# AmazonDash.net
KiCad netlist of a schematic drawn in EAGLE
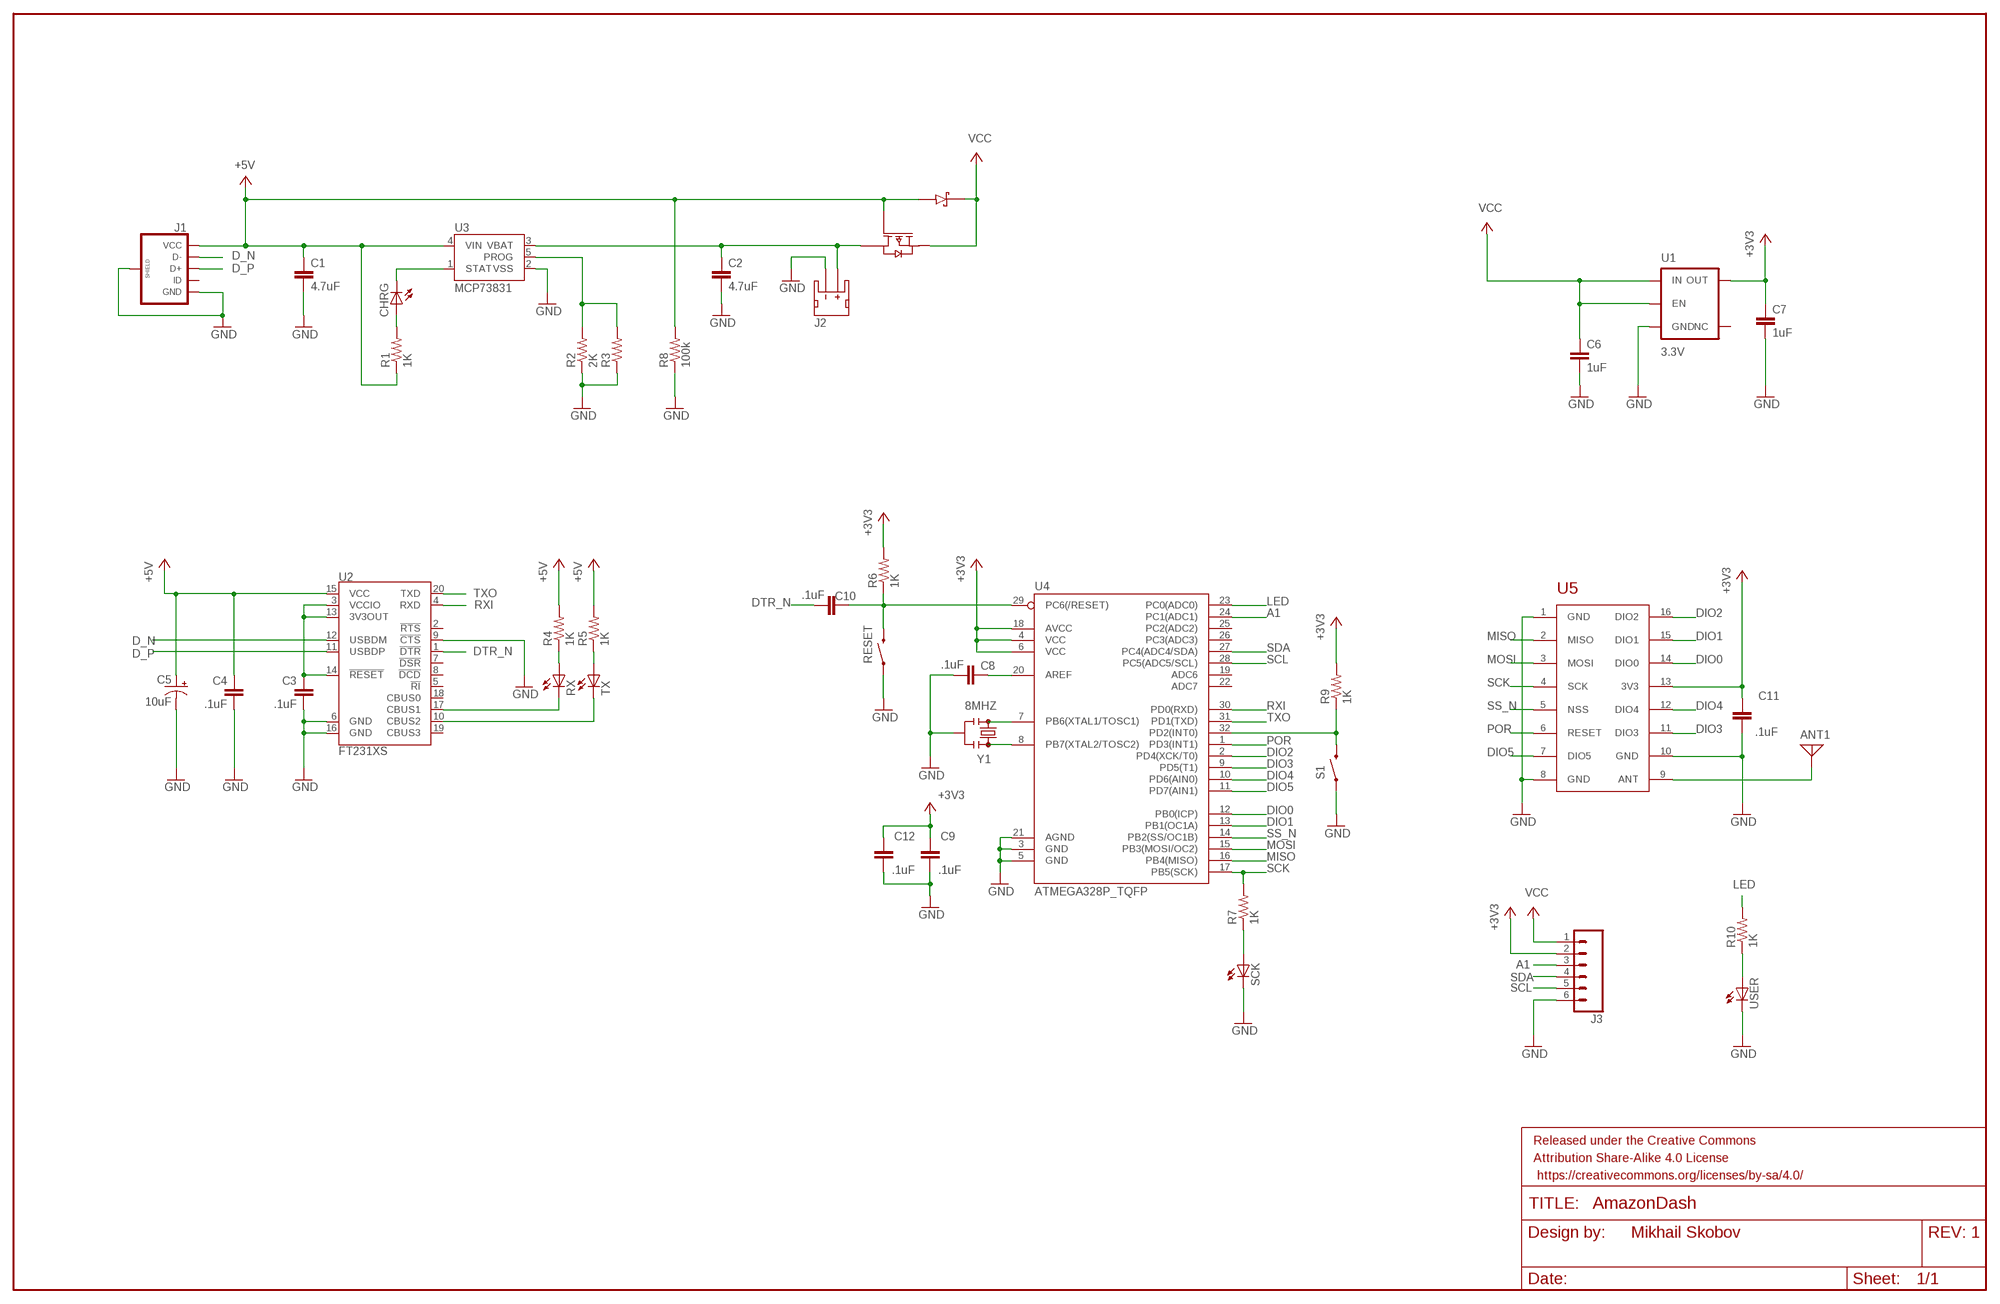
[diagram p0: schematic, sheet 1]

(export (version "E")
  (design (tool "Eeschema 10.0.6"))
  (components
    (comp (ref "ANT1")
      (value "ANTENNA")
      (footprint "eagle-import:PAD-01")
      (libsource (lib "eagle-import") (part "ANTENNA"))
    )
    (comp (ref "C1")
      (value "4.7uF")
      (footprint "eagle-import:C0805")
      (libsource (lib "eagle-import") (part "C-EUC0805"))
    )
    (comp (ref "C2")
      (value "4.7uF")
      (footprint "eagle-import:C0805")
      (libsource (lib "eagle-import") (part "C-EUC0805"))
    )
    (comp (ref "C3")
      (value ".1uF")
      (footprint "eagle-import:C0805")
      (libsource (lib "eagle-import") (part "C-EUC0805"))
    )
    (comp (ref "C4")
      (value ".1uF")
      (footprint "eagle-import:C0805")
      (libsource (lib "eagle-import") (part "C-EUC0805"))
    )
    (comp (ref "C5")
      (value "10uF")
      (footprint "eagle-import:EIA3216")
      (libsource (lib "eagle-import") (part "10UF-16V-10%(TANT)"))
    )
    (comp (ref "C6")
      (value "1uF")
      (footprint "eagle-import:C0805")
      (libsource (lib "eagle-import") (part "C-EUC0805"))
    )
    (comp (ref "C7")
      (value "1uF")
      (footprint "eagle-import:C0805")
      (libsource (lib "eagle-import") (part "C-EUC0805"))
    )
    (comp (ref "C8")
      (value ".1uF")
      (footprint "eagle-import:C0805")
      (libsource (lib "eagle-import") (part "C-EUC0805"))
    )
    (comp (ref "C9")
      (value ".1uF")
      (footprint "eagle-import:C0805")
      (libsource (lib "eagle-import") (part "C-EUC0805"))
    )
    (comp (ref "C10")
      (value ".1uF")
      (footprint "eagle-import:C0805")
      (libsource (lib "eagle-import") (part "C-EUC0805"))
    )
    (comp (ref "C11")
      (value ".1uF")
      (footprint "eagle-import:C0805")
      (libsource (lib "eagle-import") (part "C-EUC0805"))
    )
    (comp (ref "C12")
      (value ".1uF")
      (footprint "eagle-import:C0805")
      (libsource (lib "eagle-import") (part "C-EUC0805"))
    )
    (comp (ref "CHRG")
      (value "LEDCHIPLED_0805")
      (footprint "eagle-import:CHIPLED_0805")
      (libsource (lib "eagle-import") (part "LEDCHIPLED_0805"))
    )
    (comp (ref "FRAME2")
      (value "FRAME-LEDGER")
      (footprint "eagle-import:CREATIVE_COMMONS")
      (libsource (lib "eagle-import") (part "FRAME-LEDGER"))
    )
    (comp (ref "J1")
      (value "USB_MICROB_PLUGCONN-11752")
      (footprint "eagle-import:USB-B-MICRO-SMD_V03")
      (libsource (lib "eagle-import") (part "USB_MICROB_PLUGCONN-11752"))
    )
    (comp (ref "J2")
      (value "JST_2MM_MALE")
      (footprint "eagle-import:JST-2-SMD")
      (libsource (lib "eagle-import") (part "JST_2MM_MALE"))
    )
    (comp (ref "J3")
      (value "M06LOCK")
      (footprint "eagle-import:1X06_LOCK")
      (libsource (lib "eagle-import") (part "M06LOCK"))
    )
    (comp (ref "R1")
      (value "1K")
      (footprint "eagle-import:R0805")
      (libsource (lib "eagle-import") (part "R-US_R0805"))
    )
    (comp (ref "R2")
      (value "2K")
      (footprint "eagle-import:R0805")
      (libsource (lib "eagle-import") (part "R-US_R0805"))
    )
    (comp (ref "R3")
      (value "R-US_R0805")
      (footprint "eagle-import:R0805")
      (libsource (lib "eagle-import") (part "R-US_R0805"))
    )
    (comp (ref "R4")
      (value "1K")
      (footprint "eagle-import:R0805")
      (libsource (lib "eagle-import") (part "R-US_R0805"))
    )
    (comp (ref "R5")
      (value "1K")
      (footprint "eagle-import:R0805")
      (libsource (lib "eagle-import") (part "R-US_R0805"))
    )
    (comp (ref "R6")
      (value "1K")
      (footprint "eagle-import:R0805")
      (libsource (lib "eagle-import") (part "R-US_R0805"))
    )
    (comp (ref "R7")
      (value "1K")
      (footprint "eagle-import:R0805")
      (libsource (lib "eagle-import") (part "R-US_R0805"))
    )
    (comp (ref "R8")
      (value "100k")
      (footprint "eagle-import:R0805")
      (libsource (lib "eagle-import") (part "R-US_R0805"))
    )
    (comp (ref "R9")
      (value "1K")
      (footprint "eagle-import:R0805")
      (libsource (lib "eagle-import") (part "R-US_R0805"))
    )
    (comp (ref "R10")
      (value "1K")
      (footprint "eagle-import:R0805")
      (libsource (lib "eagle-import") (part "R-US_R0805"))
    )
    (comp (ref "RESET")
      (value "SWITCH-MOMENTARY-2SMD")
      (footprint "eagle-import:TACTILE-SWITCH-SMD")
      (libsource (lib "eagle-import") (part "SWITCH-MOMENTARY-2SMD"))
    )
    (comp (ref "RX")
      (value "LEDCHIPLED_0805")
      (footprint "eagle-import:CHIPLED_0805")
      (libsource (lib "eagle-import") (part "LEDCHIPLED_0805"))
    )
    (comp (ref "S1")
      (value "SWITCH-MOMENTARY-2SMD")
      (footprint "eagle-import:TACTILE-SWITCH-SMD")
      (libsource (lib "eagle-import") (part "SWITCH-MOMENTARY-2SMD"))
    )
    (comp (ref "SCK")
      (value "LEDCHIPLED_0805")
      (footprint "eagle-import:CHIPLED_0805")
      (libsource (lib "eagle-import") (part "LEDCHIPLED_0805"))
    )
    (comp (ref "TX")
      (value "LEDCHIPLED_0805")
      (footprint "eagle-import:CHIPLED_0805")
      (libsource (lib "eagle-import") (part "LEDCHIPLED_0805"))
    )
    (comp (ref "U1")
      (value "3.3V")
      (footprint "eagle-import:SOT23-5")
      (libsource (lib "eagle-import") (part "V_REG_AP2112K-3.3V"))
    )
    (comp (ref "U2")
      (value "FT231XS")
      (footprint "eagle-import:SSOP20_L")
      (libsource (lib "eagle-import") (part "FT231XS"))
    )
    (comp (ref "U3")
      (value "MCP73831")
      (footprint "eagle-import:SOT23-5")
      (libsource (lib "eagle-import") (part "MCP73831"))
    )
    (comp (ref "U4")
      (value "ATMEGA328P_TQFP")
      (footprint "eagle-import:TQFP32-08")
      (libsource (lib "eagle-import") (part "ATMEGA328P_TQFP"))
    )
    (comp (ref "U5")
      (value "RFM69HCW")
      (footprint "eagle-import:RFM69")
      (libsource (lib "eagle-import") (part "RFM69HCW"))
    )
    (comp (ref "U6")
      (value "FDC6392S")
      (footprint "eagle-import:SSOT-6")
      (libsource (lib "eagle-import") (part "FDC6392S"))
    )
    (comp (ref "USER")
      (value "LEDCHIPLED_0805")
      (footprint "eagle-import:CHIPLED_0805")
      (libsource (lib "eagle-import") (part "LEDCHIPLED_0805"))
    )
    (comp (ref "Y1")
      (value "8MHZ")
      (footprint "eagle-import:RESONATOR-SMD")
      (libsource (lib "eagle-import") (part "RESONATOR8MHZ"))
    )
  )
  (nets
    (net (code "1") (name "+3V3") (class "Default")
      (node (ref "C11") (pin "2") (pinfunction "2_2") (pintype "passive"))
      (node (ref "C12") (pin "2") (pinfunction "2_2") (pintype "passive"))
      (node (ref "C7") (pin "1") (pinfunction "1_1") (pintype "passive"))
      (node (ref "C9") (pin "2") (pinfunction "2_2") (pintype "passive"))
      (node (ref "J3") (pin "2") (pinfunction "2_2") (pintype "passive"))
      (node (ref "R6") (pin "2") (pinfunction "2_2") (pintype "passive"))
      (node (ref "R9") (pin "2") (pinfunction "2_2") (pintype "passive"))
      (node (ref "U1") (pin "5") (pinfunction "OUT_5") (pintype "passive"))
      (node (ref "U4") (pin "18") (pinfunction "AVCC_18") (pintype "bidirectional"))
      (node (ref "U4") (pin "4") (pinfunction "VCC_4") (pintype "bidirectional"))
      (node (ref "U4") (pin "6") (pinfunction "VCC_6") (pintype "bidirectional"))
      (node (ref "U5") (pin "13") (pinfunction "3V3_13") (pintype "power_in"))
    )
    (net (code "2") (name "+5V") (class "Default")
      (node (ref "C1") (pin "1") (pinfunction "1_1") (pintype "passive"))
      (node (ref "C4") (pin "1") (pinfunction "1_1") (pintype "passive"))
      (node (ref "C5") (pin "A") (pinfunction "+_A") (pintype "passive"))
      (node (ref "J1") (pin "VBUS") (pinfunction "VCC_VBUS") (pintype "bidirectional"))
      (node (ref "R1") (pin "1") (pinfunction "1_1") (pintype "passive"))
      (node (ref "R4") (pin "2") (pinfunction "2_2") (pintype "passive"))
      (node (ref "R5") (pin "2") (pinfunction "2_2") (pintype "passive"))
      (node (ref "R8") (pin "2") (pinfunction "2_2") (pintype "passive"))
      (node (ref "U2") (pin "15") (pinfunction "VCC_15") (pintype "bidirectional"))
      (node (ref "U3") (pin "4") (pinfunction "VIN_4") (pintype "power_in"))
      (node (ref "U6") (pin "1") (pinfunction "A_1") (pintype "bidirectional"))
      (node (ref "U6") (pin "3") (pinfunction "G_3") (pintype "bidirectional"))
    )
    (net (code "3") (name "/A1") (class "Default")
      (node (ref "J3") (pin "3") (pinfunction "3_3") (pintype "passive"))
      (node (ref "U4") (pin "24") (pinfunction "PC1(ADC1)_24") (pintype "bidirectional"))
    )
    (net (code "4") (name "/DIO0") (class "Default")
      (node (ref "U4") (pin "12") (pinfunction "PB0(ICP)_12") (pintype "bidirectional"))
      (node (ref "U5") (pin "14") (pinfunction "DIO0_14") (pintype "bidirectional"))
    )
    (net (code "5") (name "/DIO1") (class "Default")
      (node (ref "U4") (pin "13") (pinfunction "PB1(OC1A)_13") (pintype "bidirectional"))
      (node (ref "U5") (pin "15") (pinfunction "DIO1_15") (pintype "bidirectional"))
    )
    (net (code "6") (name "/DIO2") (class "Default")
      (node (ref "U4") (pin "2") (pinfunction "PD4(XCK/T0)_2") (pintype "bidirectional"))
      (node (ref "U5") (pin "16") (pinfunction "DIO2_16") (pintype "bidirectional"))
    )
    (net (code "7") (name "/DIO3") (class "Default")
      (node (ref "U4") (pin "9") (pinfunction "PD5(T1)_9") (pintype "bidirectional"))
      (node (ref "U5") (pin "11") (pinfunction "DIO3_11") (pintype "bidirectional"))
    )
    (net (code "8") (name "/DIO4") (class "Default")
      (node (ref "U4") (pin "10") (pinfunction "PD6(AIN0)_10") (pintype "bidirectional"))
      (node (ref "U5") (pin "12") (pinfunction "DIO4_12") (pintype "bidirectional"))
    )
    (net (code "9") (name "/DIO5") (class "Default")
      (node (ref "U4") (pin "11") (pinfunction "PD7(AIN1)_11") (pintype "bidirectional"))
      (node (ref "U5") (pin "7") (pinfunction "DIO5_7") (pintype "bidirectional"))
    )
    (net (code "10") (name "/DTR_N") (class "Default")
      (node (ref "C10") (pin "1") (pinfunction "1_1") (pintype "passive"))
      (node (ref "U2") (pin "1") (pinfunction "~{DTR}_1") (pintype "bidirectional"))
    )
    (net (code "11") (name "/D_N") (class "Default")
      (node (ref "J1") (pin "D-") (pinfunction "D-_D-") (pintype "bidirectional"))
      (node (ref "U2") (pin "12") (pinfunction "USBDM_12") (pintype "bidirectional"))
    )
    (net (code "12") (name "/D_P") (class "Default")
      (node (ref "J1") (pin "D+") (pinfunction "D+_D+") (pintype "bidirectional"))
      (node (ref "U2") (pin "11") (pinfunction "USBDP_11") (pintype "bidirectional"))
    )
    (net (code "13") (name "/LED") (class "Default")
      (node (ref "R10") (pin "2") (pinfunction "2_2") (pintype "passive"))
      (node (ref "U4") (pin "23") (pinfunction "PC0(ADC0)_23") (pintype "bidirectional"))
    )
    (net (code "14") (name "/MISO") (class "Default")
      (node (ref "U4") (pin "16") (pinfunction "PB4(MISO)_16") (pintype "bidirectional"))
      (node (ref "U5") (pin "2") (pinfunction "MISO_2") (pintype "bidirectional"))
    )
    (net (code "15") (name "/MOSI") (class "Default")
      (node (ref "U4") (pin "15") (pinfunction "PB3(MOSI/OC2)_15") (pintype "bidirectional"))
      (node (ref "U5") (pin "3") (pinfunction "MOSI_3") (pintype "bidirectional"))
    )
    (net (code "16") (name "/POR") (class "Default")
      (node (ref "U4") (pin "1") (pinfunction "PD3(INT1)_1") (pintype "bidirectional"))
      (node (ref "U5") (pin "6") (pinfunction "RESET_6") (pintype "bidirectional"))
    )
    (net (code "17") (name "/RXI") (class "Default")
      (node (ref "U2") (pin "4") (pinfunction "RXD_4") (pintype "bidirectional"))
      (node (ref "U4") (pin "30") (pinfunction "PD0(RXD)_30") (pintype "bidirectional"))
    )
    (net (code "18") (name "/SCK") (class "Default")
      (node (ref "R7") (pin "2") (pinfunction "2_2") (pintype "passive"))
      (node (ref "U4") (pin "17") (pinfunction "PB5(SCK)_17") (pintype "bidirectional"))
      (node (ref "U5") (pin "4") (pinfunction "SCK_4") (pintype "bidirectional"))
    )
    (net (code "19") (name "/SCL") (class "Default")
      (node (ref "J3") (pin "5") (pinfunction "5_5") (pintype "passive"))
      (node (ref "U4") (pin "28") (pinfunction "PC5(ADC5/SCL)_28") (pintype "bidirectional"))
    )
    (net (code "20") (name "/SDA") (class "Default")
      (node (ref "J3") (pin "4") (pinfunction "4_4") (pintype "passive"))
      (node (ref "U4") (pin "27") (pinfunction "PC4(ADC4/SDA)_27") (pintype "bidirectional"))
    )
    (net (code "21") (name "/SS_N") (class "Default")
      (node (ref "U4") (pin "14") (pinfunction "PB2(SS/OC1B)_14") (pintype "bidirectional"))
      (node (ref "U5") (pin "5") (pinfunction "NSS_5") (pintype "bidirectional"))
    )
    (net (code "22") (name "/TXO") (class "Default")
      (node (ref "U2") (pin "20") (pinfunction "TXD_20") (pintype "bidirectional"))
      (node (ref "U4") (pin "31") (pinfunction "PD1(TXD)_31") (pintype "bidirectional"))
    )
    (net (code "23") (name "GND") (class "Default")
      (node (ref "C1") (pin "2") (pinfunction "2_2") (pintype "passive"))
      (node (ref "C11") (pin "1") (pinfunction "1_1") (pintype "passive"))
      (node (ref "C12") (pin "1") (pinfunction "1_1") (pintype "passive"))
      (node (ref "C2") (pin "2") (pinfunction "2_2") (pintype "passive"))
      (node (ref "C3") (pin "2") (pinfunction "2_2") (pintype "passive"))
      (node (ref "C4") (pin "2") (pinfunction "2_2") (pintype "passive"))
      (node (ref "C5") (pin "C") (pinfunction "-_C") (pintype "passive"))
      (node (ref "C6") (pin "2") (pinfunction "2_2") (pintype "passive"))
      (node (ref "C7") (pin "2") (pinfunction "2_2") (pintype "passive"))
      (node (ref "C8") (pin "1") (pinfunction "1_1") (pintype "passive"))
      (node (ref "C9") (pin "1") (pinfunction "1_1") (pintype "passive"))
      (node (ref "J1") (pin "GND") (pinfunction "GND_GND") (pintype "bidirectional"))
      (node (ref "J1") (pin "SHIELD1") (pinfunction "SHIELD_SHIELD1") (pintype "bidirectional"))
      (node (ref "J1") (pin "SHIELD2") (pinfunction "SHIELD_SHIELD2") (pintype "bidirectional"))
      (node (ref "J1") (pin "SHIELD3") (pinfunction "SHIELD_SHIELD3") (pintype "bidirectional"))
      (node (ref "J2") (pin "1") (pinfunction "-_1") (pintype "bidirectional"))
      (node (ref "J3") (pin "6") (pinfunction "6_6") (pintype "passive"))
      (node (ref "R2") (pin "1") (pinfunction "1_1") (pintype "passive"))
      (node (ref "R3") (pin "1") (pinfunction "1_1") (pintype "passive"))
      (node (ref "R8") (pin "1") (pinfunction "1_1") (pintype "passive"))
      (node (ref "RESET") (pin "1") (pinfunction "1_1") (pintype "passive"))
      (node (ref "S1") (pin "1") (pinfunction "1_1") (pintype "passive"))
      (node (ref "SCK") (pin "C") (pinfunction "C_C") (pintype "passive"))
      (node (ref "U1") (pin "2") (pinfunction "GND_2") (pintype "input"))
      (node (ref "U2") (pin "16") (pinfunction "GND_16") (pintype "bidirectional"))
      (node (ref "U2") (pin "6") (pinfunction "GND_6") (pintype "bidirectional"))
      (node (ref "U2") (pin "9") (pinfunction "~{CTS}_9") (pintype "bidirectional"))
      (node (ref "U3") (pin "2") (pinfunction "VSS_2") (pintype "power_in"))
      (node (ref "U4") (pin "21") (pinfunction "AGND_21") (pintype "bidirectional"))
      (node (ref "U4") (pin "3") (pinfunction "GND_3") (pintype "bidirectional"))
      (node (ref "U4") (pin "5") (pinfunction "GND_5") (pintype "bidirectional"))
      (node (ref "U5") (pin "1") (pinfunction "GND_1") (pintype "power_in"))
      (node (ref "U5") (pin "10") (pinfunction "GND_10") (pintype "power_in"))
      (node (ref "U5") (pin "8") (pinfunction "GND_8") (pintype "power_in"))
      (node (ref "USER") (pin "C") (pinfunction "C_C") (pintype "passive"))
      (node (ref "Y1") (pin "2") (pinfunction "2_2") (pintype "passive"))
    )
    (net (code "24") (name "Net-(CHRG-PadA)") (class "Default")
      (node (ref "CHRG") (pin "A") (pinfunction "A_A") (pintype "passive"))
      (node (ref "R1") (pin "2") (pinfunction "2_2") (pintype "passive"))
    )
    (net (code "25") (name "Net-(J2-+)") (class "Default")
      (node (ref "C2") (pin "1") (pinfunction "1_1") (pintype "passive"))
      (node (ref "J2") (pin "2") (pinfunction "+_2") (pintype "bidirectional"))
      (node (ref "U3") (pin "3") (pinfunction "VBAT_3") (pintype "power_in"))
      (node (ref "U6") (pin "4") (pinfunction "S_4") (pintype "bidirectional"))
    )
    (net (code "26") (name "Net-(R4-Pad1)") (class "Default")
      (node (ref "R4") (pin "1") (pinfunction "1_1") (pintype "passive"))
      (node (ref "RX") (pin "A") (pinfunction "A_A") (pintype "passive"))
    )
    (net (code "27") (name "Net-(R5-Pad1)") (class "Default")
      (node (ref "R5") (pin "1") (pinfunction "1_1") (pintype "passive"))
      (node (ref "TX") (pin "A") (pinfunction "A_A") (pintype "passive"))
    )
    (net (code "28") (name "Net-(R7-Pad1)") (class "Default")
      (node (ref "R7") (pin "1") (pinfunction "1_1") (pintype "passive"))
      (node (ref "SCK") (pin "A") (pinfunction "A_A") (pintype "passive"))
    )
    (net (code "29") (name "Net-(R10-Pad1)") (class "Default")
      (node (ref "R10") (pin "1") (pinfunction "1_1") (pintype "passive"))
      (node (ref "USER") (pin "A") (pinfunction "A_A") (pintype "passive"))
    )
    (net (code "30") (name "Net-(RESET-2)") (class "Default")
      (node (ref "C10") (pin "2") (pinfunction "2_2") (pintype "passive"))
      (node (ref "R6") (pin "1") (pinfunction "1_1") (pintype "passive"))
      (node (ref "RESET") (pin "3") (pinfunction "2_3") (pintype "passive"))
      (node (ref "U4") (pin "29") (pinfunction "PC6(/RESET)_29") (pintype "bidirectional"))
    )
    (net (code "31") (name "Net-(S1-2)") (class "Default")
      (node (ref "R9") (pin "1") (pinfunction "1_1") (pintype "passive"))
      (node (ref "S1") (pin "3") (pinfunction "2_3") (pintype "passive"))
      (node (ref "U4") (pin "32") (pinfunction "PD2(INT0)_32") (pintype "bidirectional"))
    )
    (net (code "32") (name "Net-(U2-3V3OUT)") (class "Default")
      (node (ref "C3") (pin "1") (pinfunction "1_1") (pintype "passive"))
      (node (ref "U2") (pin "13") (pinfunction "3V3OUT_13") (pintype "bidirectional"))
      (node (ref "U2") (pin "14") (pinfunction "~{RESET}_14") (pintype "bidirectional"))
      (node (ref "U2") (pin "3") (pinfunction "VCCIO_3") (pintype "bidirectional"))
    )
    (net (code "33") (name "Net-(U2-CBUS1)") (class "Default")
      (node (ref "RX") (pin "C") (pinfunction "C_C") (pintype "passive"))
      (node (ref "U2") (pin "17") (pinfunction "CBUS1_17") (pintype "bidirectional"))
    )
    (net (code "34") (name "Net-(U2-CBUS2)") (class "Default")
      (node (ref "TX") (pin "C") (pinfunction "C_C") (pintype "passive"))
      (node (ref "U2") (pin "10") (pinfunction "CBUS2_10") (pintype "bidirectional"))
    )
    (net (code "35") (name "Net-(U3-PROG)") (class "Default")
      (node (ref "R2") (pin "2") (pinfunction "2_2") (pintype "passive"))
      (node (ref "R3") (pin "2") (pinfunction "2_2") (pintype "passive"))
      (node (ref "U3") (pin "5") (pinfunction "PROG_5") (pintype "input"))
    )
    (net (code "36") (name "Net-(U3-STAT)") (class "Default")
      (node (ref "CHRG") (pin "C") (pinfunction "C_C") (pintype "passive"))
      (node (ref "U3") (pin "1") (pinfunction "STAT_1") (pintype "output"))
    )
    (net (code "37") (name "Net-(U4-AREF)") (class "Default")
      (node (ref "C8") (pin "2") (pinfunction "2_2") (pintype "passive"))
      (node (ref "U4") (pin "20") (pinfunction "AREF_20") (pintype "bidirectional"))
    )
    (net (code "38") (name "Net-(U4-PB6(XTAL1{slash}TOSC1))") (class "Default")
      (node (ref "U4") (pin "7") (pinfunction "PB6(XTAL1/TOSC1)_7") (pintype "bidirectional"))
      (node (ref "Y1") (pin "1") (pinfunction "1_1") (pintype "passive"))
    )
    (net (code "39") (name "Net-(U4-PB7(XTAL2{slash}TOSC2))") (class "Default")
      (node (ref "U4") (pin "8") (pinfunction "PB7(XTAL2/TOSC2)_8") (pintype "bidirectional"))
      (node (ref "Y1") (pin "3") (pinfunction "3_3") (pintype "passive"))
    )
    (net (code "40") (name "Net-(U5-ANT)") (class "Default")
      (node (ref "ANT1") (pin "1") (pinfunction "1_1") (pintype "output"))
      (node (ref "U5") (pin "9") (pinfunction "ANT_9") (pintype "bidirectional"))
    )
    (net (code "41") (name "VCC") (class "Default")
      (node (ref "C6") (pin "1") (pinfunction "1_1") (pintype "passive"))
      (node (ref "J3") (pin "1") (pinfunction "1_1") (pintype "passive"))
      (node (ref "U1") (pin "1") (pinfunction "IN_1") (pintype "input"))
      (node (ref "U1") (pin "3") (pinfunction "EN_3") (pintype "input"))
      (node (ref "U6") (pin "2") (pinfunction "D_2") (pintype "bidirectional"))
      (node (ref "U6") (pin "6") (pinfunction "C_6") (pintype "bidirectional"))
    )
    (net (code "42") (name "unconnected-(J1-PadID)") (class "Default")
      (node (ref "J1") (pin "ID") (pinfunction "ID_ID") (pintype "bidirectional"))
    )
    (net (code "43") (name "unconnected-(J2-PAD1-PadNC1)") (class "Default")
      (node (ref "J2") (pin "NC1") (pinfunction "PAD1_NC1") (pintype "bidirectional"))
    )
    (net (code "44") (name "unconnected-(J2-PAD2-PadNC2)") (class "Default")
      (node (ref "J2") (pin "NC2") (pinfunction "PAD2_NC2") (pintype "bidirectional"))
    )
    (net (code "45") (name "unconnected-(U1-NC-Pad4)") (class "Default")
      (node (ref "U1") (pin "4") (pinfunction "NC_4") (pintype "input"))
    )
    (net (code "46") (name "unconnected-(U2-CBUS0-Pad18)") (class "Default")
      (node (ref "U2") (pin "18") (pinfunction "CBUS0_18") (pintype "bidirectional"))
    )
    (net (code "47") (name "unconnected-(U2-CBUS3-Pad19)") (class "Default")
      (node (ref "U2") (pin "19") (pinfunction "CBUS3_19") (pintype "bidirectional"))
    )
    (net (code "48") (name "unconnected-(U2-~{DCD}-Pad8)") (class "Default")
      (node (ref "U2") (pin "8") (pinfunction "~{DCD}_8") (pintype "bidirectional"))
    )
    (net (code "49") (name "unconnected-(U2-~{DSR}-Pad7)") (class "Default")
      (node (ref "U2") (pin "7") (pinfunction "~{DSR}_7") (pintype "bidirectional"))
    )
    (net (code "50") (name "unconnected-(U2-~{RI}-Pad5)") (class "Default")
      (node (ref "U2") (pin "5") (pinfunction "~{RI}_5") (pintype "bidirectional"))
    )
    (net (code "51") (name "unconnected-(U2-~{RTS}-Pad2)") (class "Default")
      (node (ref "U2") (pin "2") (pinfunction "~{RTS}_2") (pintype "bidirectional"))
    )
    (net (code "52") (name "unconnected-(U4-ADC6-Pad19)") (class "Default")
      (node (ref "U4") (pin "19") (pinfunction "ADC6_19") (pintype "bidirectional"))
    )
    (net (code "53") (name "unconnected-(U4-ADC7-Pad22)") (class "Default")
      (node (ref "U4") (pin "22") (pinfunction "ADC7_22") (pintype "bidirectional"))
    )
    (net (code "54") (name "unconnected-(U4-PC2(ADC2)-Pad25)") (class "Default")
      (node (ref "U4") (pin "25") (pinfunction "PC2(ADC2)_25") (pintype "bidirectional"))
    )
    (net (code "55") (name "unconnected-(U4-PC3(ADC3)-Pad26)") (class "Default")
      (node (ref "U4") (pin "26") (pinfunction "PC3(ADC3)_26") (pintype "bidirectional"))
    )
  )
)
